# Voltage_Reference_Circuit.net
KiCad netlist of a schematic drawn in Altium Designer
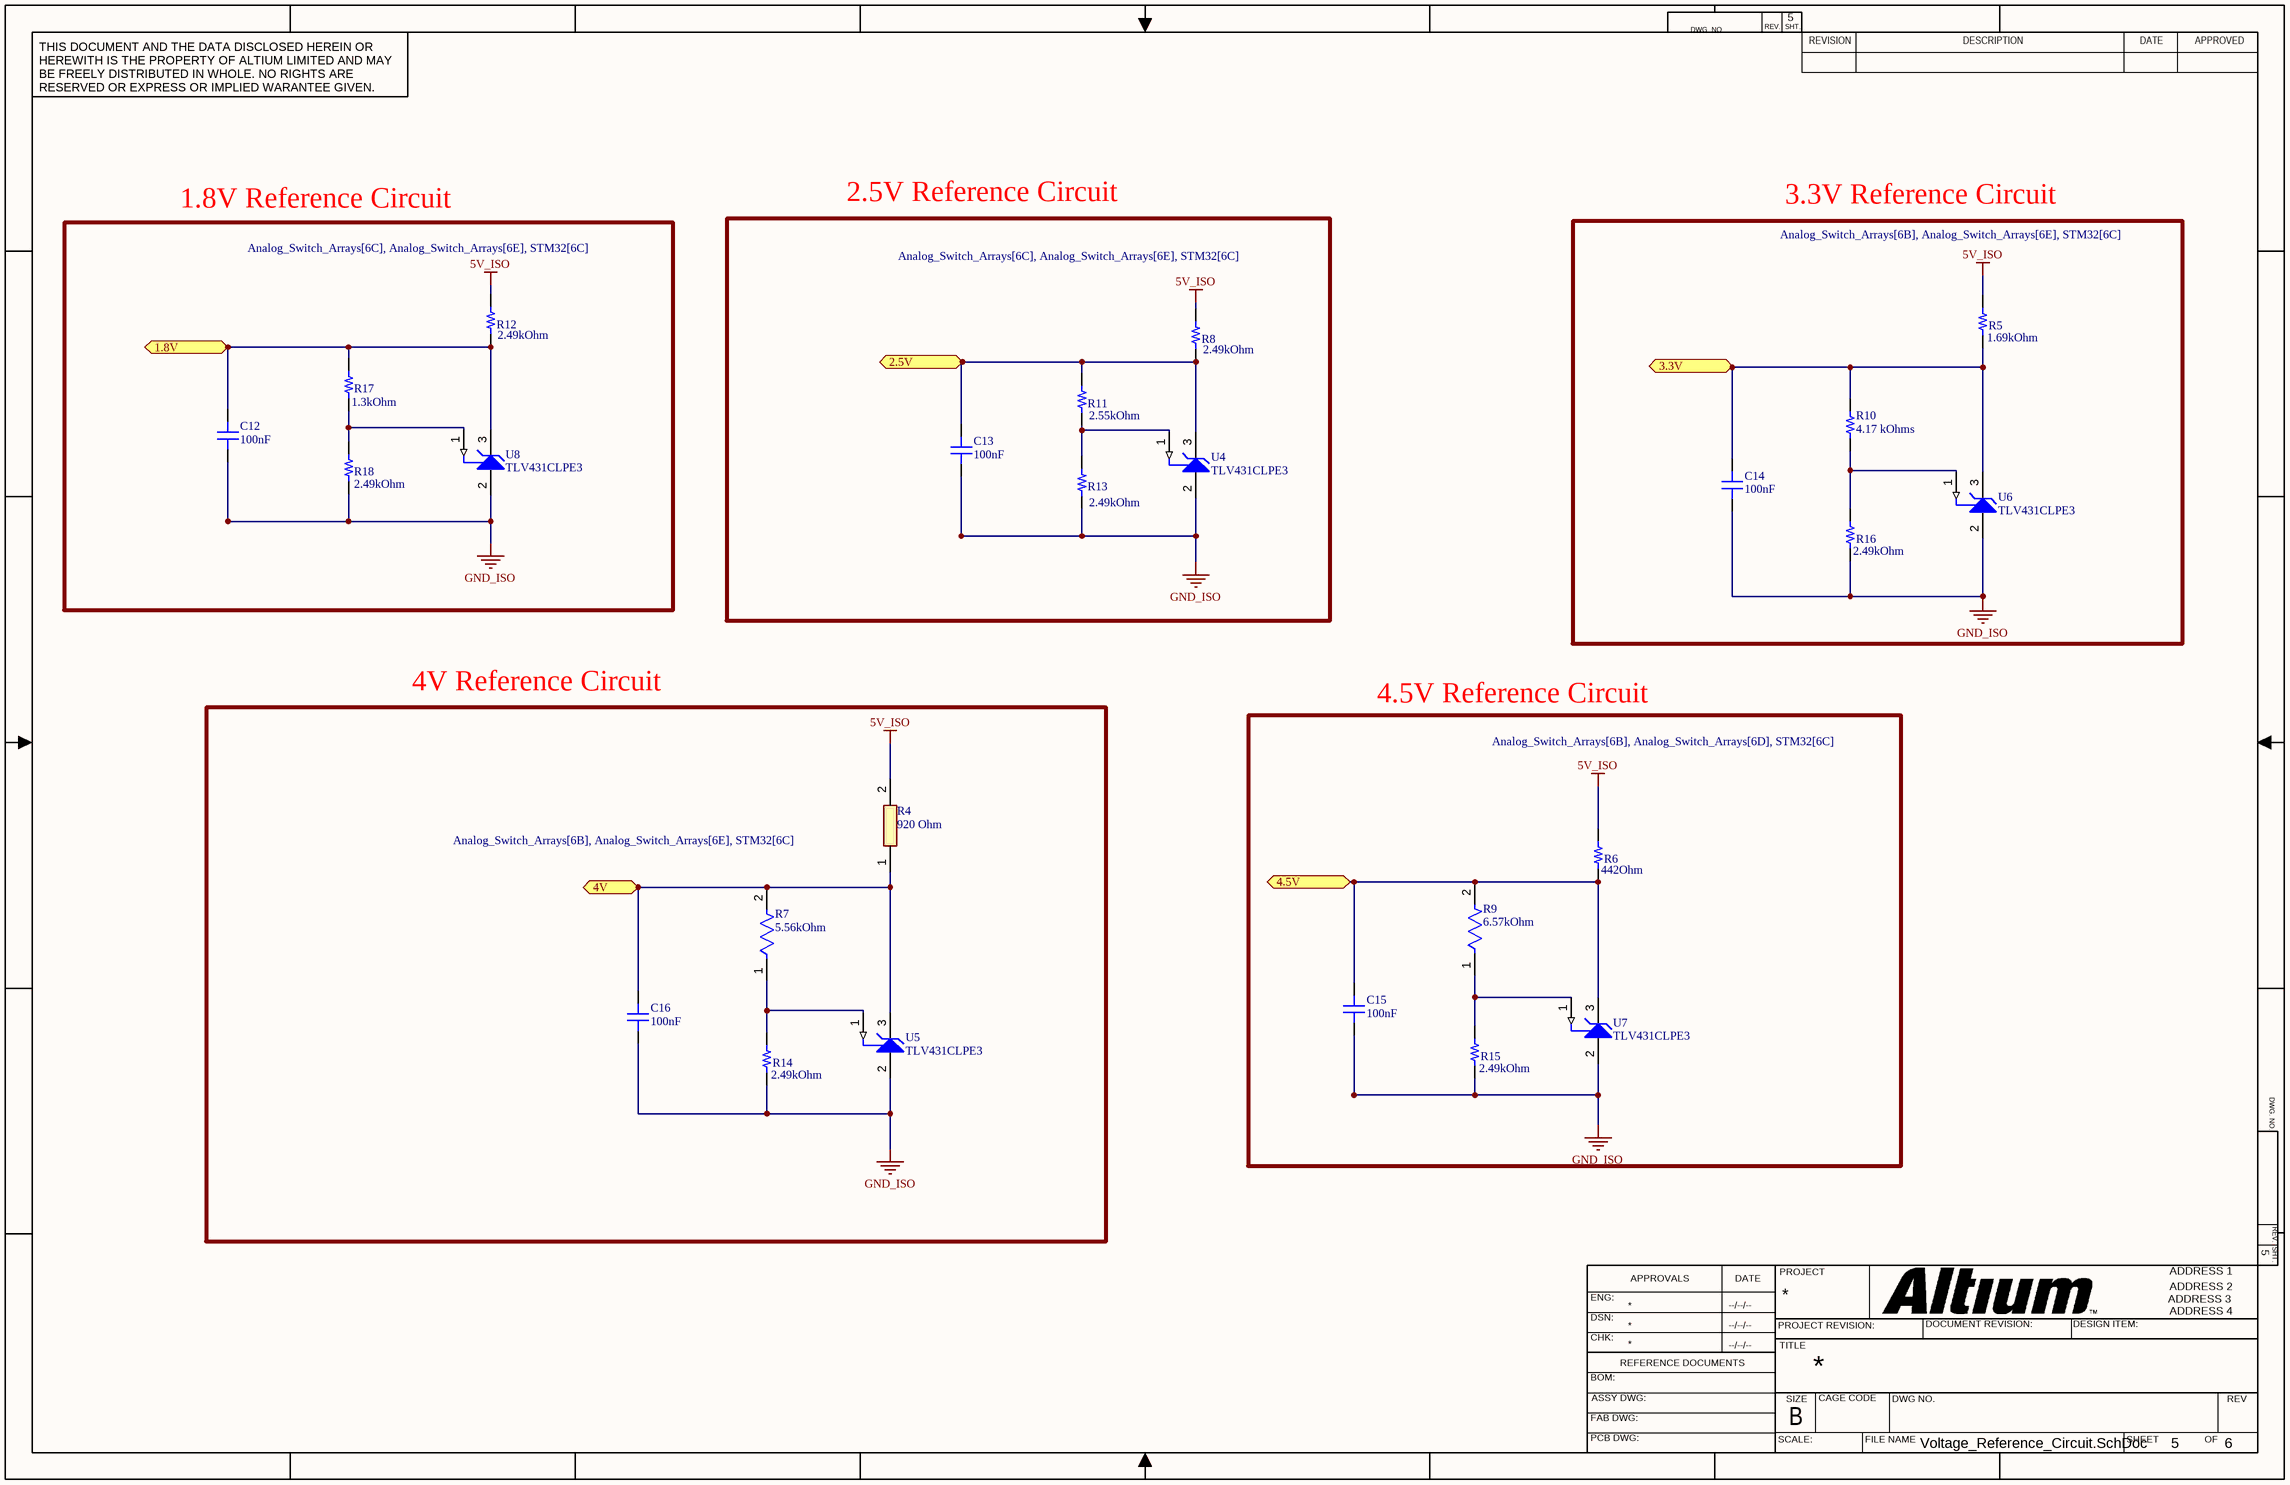
[diagram p0: Voltage_Reference_Circuit.SchDoc]

(export (version "E")
  (design (tool "Eeschema 10.0.6"))
  (components
    (comp (ref "C12")
      (value "100nF")
      (footprint "CAP 1206_3216 - 0.8MM")
      (description "CAP CER 0.1UF 25V X7R 1206")
      (fields (field (name "PART NUMBER") "VJ1206Y104KXXAC"))
      (libsource (lib "University of Massachusetts Lowell") (part "CAPACITOR"))
    )
    (comp (ref "C13")
      (value "100nF")
      (footprint "CAP 1206_3216 - 0.8MM")
      (description "CAP CER 0.1UF 25V X7R 1206")
      (fields (field (name "PART NUMBER") "VJ1206Y104KXXAC"))
      (libsource (lib "University of Massachusetts Lowell") (part "CAPACITOR"))
    )
    (comp (ref "C14")
      (value "100nF")
      (footprint "CAP 1206_3216 - 0.8MM")
      (description "CAP CER 0.1UF 25V X7R 1206")
      (fields (field (name "PART NUMBER") "VJ1206Y104KXXAC"))
      (libsource (lib "University of Massachusetts Lowell") (part "CAPACITOR"))
    )
    (comp (ref "C15")
      (value "100nF")
      (footprint "CAP 1206_3216 - 0.8MM")
      (description "CAP CER 0.1UF 25V X7R 1206")
      (fields (field (name "PART NUMBER") "VJ1206Y104KXXAC"))
      (libsource (lib "University of Massachusetts Lowell") (part "CAPACITOR"))
    )
    (comp (ref "C16")
      (value "100nF")
      (footprint "CAP 1206_3216 - 0.8MM")
      (description "CAP CER 0.1UF 25V X7R 1206")
      (fields (field (name "PART NUMBER") "VJ1206Y104KXXAC"))
      (libsource (lib "University of Massachusetts Lowell") (part "CAPACITOR"))
    )
    (comp (ref "R4")
      (value "920 Ohm")
      (footprint "SamacSys:RESC1608X55N")
      (description "Resistor")
      (fields (field (name "MANUFACTURER_PART_NUMBER") "UPTF0603-16W-N-1781FT"))
      (libsource (lib "*") (part "UPTF0603-16W-N-1781FT"))
    )
    (comp (ref "R5")
      (value "1.69kOhm")
      (footprint "RES 1206_3216")
      (description "RES 1.69 KOHMS 0.1% 0.4W 1206")
      (fields (field (name "PART NUMBER") "RQ73C2B1K69BTD"))
      (libsource (lib "University of Massachusetts Lowell") (part "RESISTOR"))
    )
    (comp (ref "R6")
      (value "442Ohm")
      (footprint "YAGEO RES 1206_3216")
      (description "RES SMD 442 OHM 0.1% 1/4W 1206")
      (fields (field (name "PART NUMBER") "RT1206BRD07442RL"))
      (libsource (lib "University of Massachusetts Lowell") (part "RESISTOR"))
    )
    (comp (ref "R7")
      (value "5.56kOhm")
      (footprint "FP-RN73R2A-IPC_C")
      (description "5.56kΩ ±0.1% 0.125W, 1/8W Chip Resistor 0805 (2012 Metric) Moisture Resistant Thin Film")
      (libsource (lib "Altium Content Vault") (part "1029c3af85768c4190bb7ad29bc67b5"))
    )
    (comp (ref "R8")
      (value "2.49kOhm")
      (footprint "RES 1206_3216")
      (description "RES SMD 2.49K OHM 1% 1/4W 1206")
      (fields (field (name "PART NUMBER") "KTR18EZPF2491"))
      (libsource (lib "University of Massachusetts Lowell") (part "RESISTOR"))
    )
    (comp (ref "R9")
      (value "6.57kOhm")
      (footprint "FP-CRCW1206-e3-IPC_B")
      (description "RES Thick Film, 6.57kΩ, 1%, 0.25W, 100ppm/°C, 1206")
      (fields (field (name "TOLERANCE") "1%"))
      (libsource (lib "Altium Content Vault") (part "1029c3af85768c4190bb7ad29bc67b5"))
    )
    (comp (ref "R10")
      (value "4.17 kOhms")
      (footprint "KOA RES RK73 RN73 0603_1608")
      (description "RES 4.17K OHM 0.1% 1/10W 0603")
      (fields (field (name "PART NUMBER") "RN73R1JTTD4171B25"))
      (libsource (lib "University of Massachusetts Lowell") (part "RESISTOR"))
    )
    (comp (ref "R11")
      (value "2.55kOhm")
      (footprint "YAGEO RES 1206_3216")
      (description "RES SMD 2.55K OHM 0.1% 1/4W 1206")
      (fields (field (name "PART NUMBER") "RT1206BRD072K55L"))
      (libsource (lib "University of Massachusetts Lowell") (part "RESISTOR"))
    )
    (comp (ref "R12")
      (value "2.49kOhm")
      (footprint "RES 1206_3216")
      (description "RES SMD 2.49K OHM 1% 1/4W 1206")
      (fields (field (name "PART NUMBER") "KTR18EZPF2491"))
      (libsource (lib "University of Massachusetts Lowell") (part "RESISTOR"))
    )
    (comp (ref "R13")
      (value "2.49kOhm")
      (footprint "RES 1206_3216")
      (description "RES SMD 2.49K OHM 1% 1/4W 1206")
      (fields (field (name "PART NUMBER") "KTR18EZPF2491"))
      (libsource (lib "University of Massachusetts Lowell") (part "RESISTOR"))
    )
    (comp (ref "R14")
      (value "2.49kOhm")
      (footprint "RES 1206_3216")
      (description "RES SMD 2.49K OHM 1% 1/4W 1206")
      (fields (field (name "PART NUMBER") "KTR18EZPF2491"))
      (libsource (lib "University of Massachusetts Lowell") (part "RESISTOR"))
    )
    (comp (ref "R15")
      (value "2.49kOhm")
      (footprint "RES 1206_3216")
      (description "RES SMD 2.49K OHM 1% 1/4W 1206")
      (fields (field (name "PART NUMBER") "KTR18EZPF2491"))
      (libsource (lib "University of Massachusetts Lowell") (part "RESISTOR"))
    )
    (comp (ref "R16")
      (value "2.49kOhm")
      (footprint "RES 1206_3216")
      (description "RES SMD 2.49K OHM 1% 1/4W 1206")
      (fields (field (name "PART NUMBER") "KTR18EZPF2491"))
      (libsource (lib "University of Massachusetts Lowell") (part "RESISTOR"))
    )
    (comp (ref "R17")
      (value "1.3kOhm")
      (footprint "RES 1206_3216")
      (description "RES 1.13K OHM 1% 1/4W 1206")
      (fields (field (name "PART NUMBER") "RK73H2BTTD1131F"))
      (libsource (lib "University of Massachusetts Lowell") (part "RESISTOR"))
    )
    (comp (ref "R18")
      (value "2.49kOhm")
      (footprint "RES 1206_3216")
      (description "RES SMD 2.49K OHM 1% 1/4W 1206")
      (fields (field (name "PART NUMBER") "KTR18EZPF2491"))
      (libsource (lib "University of Massachusetts Lowell") (part "RESISTOR"))
    )
    (comp (ref "U4")
      (value "TLV431CLPE3")
      (footprint "TI-LP3")
      (fields (field (name "MANUFACTURER") "Texas Instruments"))
      (libsource (lib "Altium Content Vault") (part "TI-TLV431LP3"))
    )
    (comp (ref "U5")
      (value "TLV431CLPE3")
      (footprint "TI-LP3")
      (fields (field (name "MANUFACTURER") "Texas Instruments"))
      (libsource (lib "Altium Content Vault") (part "TI-TLV431LP3"))
    )
    (comp (ref "U6")
      (value "TLV431CLPE3")
      (footprint "TI-LP3")
      (fields (field (name "MANUFACTURER") "Texas Instruments"))
      (libsource (lib "Altium Content Vault") (part "TI-TLV431LP3"))
    )
    (comp (ref "U7")
      (value "TLV431CLPE3")
      (footprint "TI-LP3")
      (fields (field (name "MANUFACTURER") "Texas Instruments"))
      (libsource (lib "Altium Content Vault") (part "TI-TLV431LP3"))
    )
    (comp (ref "U8")
      (value "TLV431CLPE3")
      (footprint "TI-LP3")
      (fields (field (name "MANUFACTURER") "Texas Instruments"))
      (libsource (lib "Altium Content Vault") (part "TI-TLV431LP3"))
    )
  )
  (nets
    (net (code "1") (name "/1.8V") (class "Default")
      (node (ref "C12") (pin "2") (pinfunction "2_2") (pintype "passive"))
      (node (ref "R12") (pin "1") (pinfunction "1_1") (pintype "passive"))
      (node (ref "R17") (pin "2") (pinfunction "2_2") (pintype "passive"))
      (node (ref "U8") (pin "3") (pinfunction "CATHODE_3") (pintype "passive"))
    )
    (net (code "2") (name "/2.5V") (class "Default")
      (node (ref "C13") (pin "2") (pinfunction "2_2") (pintype "passive"))
      (node (ref "R11") (pin "2") (pinfunction "2_2") (pintype "passive"))
      (node (ref "R8") (pin "1") (pinfunction "1_1") (pintype "passive"))
      (node (ref "U4") (pin "3") (pinfunction "CATHODE_3") (pintype "passive"))
    )
    (net (code "3") (name "/3.3V") (class "Default")
      (node (ref "C14") (pin "2") (pinfunction "2_2") (pintype "passive"))
      (node (ref "R10") (pin "2") (pinfunction "2_2") (pintype "passive"))
      (node (ref "R5") (pin "1") (pinfunction "1_1") (pintype "passive"))
      (node (ref "U6") (pin "3") (pinfunction "CATHODE_3") (pintype "passive"))
    )
    (net (code "4") (name "/4.5V") (class "Default")
      (node (ref "C15") (pin "2") (pinfunction "2_2") (pintype "passive"))
      (node (ref "R6") (pin "1") (pinfunction "1_1") (pintype "passive"))
      (node (ref "R9") (pin "2") (pinfunction "2_2") (pintype "passive"))
      (node (ref "U7") (pin "3") (pinfunction "CATHODE_3") (pintype "passive"))
    )
    (net (code "5") (name "/4V") (class "Default")
      (node (ref "C16") (pin "2") (pinfunction "2_2") (pintype "passive"))
      (node (ref "R4") (pin "1") (pinfunction "1_1") (pintype "passive"))
      (node (ref "R7") (pin "2") (pinfunction "2_2") (pintype "passive"))
      (node (ref "U5") (pin "3") (pinfunction "CATHODE_3") (pintype "passive"))
    )
    (net (code "6") (name "5V_ISO") (class "Default")
      (node (ref "R12") (pin "2") (pinfunction "2_2") (pintype "passive"))
      (node (ref "R4") (pin "2") (pinfunction "2_2") (pintype "passive"))
      (node (ref "R5") (pin "2") (pinfunction "2_2") (pintype "passive"))
      (node (ref "R6") (pin "2") (pinfunction "2_2") (pintype "passive"))
      (node (ref "R8") (pin "2") (pinfunction "2_2") (pintype "passive"))
    )
    (net (code "7") (name "GND_ISO") (class "Default")
      (node (ref "C12") (pin "1") (pinfunction "1_1") (pintype "passive"))
      (node (ref "C13") (pin "1") (pinfunction "1_1") (pintype "passive"))
      (node (ref "C14") (pin "1") (pinfunction "1_1") (pintype "passive"))
      (node (ref "C15") (pin "1") (pinfunction "1_1") (pintype "passive"))
      (node (ref "C16") (pin "1") (pinfunction "1_1") (pintype "passive"))
      (node (ref "R13") (pin "1") (pinfunction "1_1") (pintype "passive"))
      (node (ref "R14") (pin "1") (pinfunction "1_1") (pintype "passive"))
      (node (ref "R15") (pin "1") (pinfunction "1_1") (pintype "passive"))
      (node (ref "R16") (pin "1") (pinfunction "1_1") (pintype "passive"))
      (node (ref "R18") (pin "1") (pinfunction "1_1") (pintype "passive"))
      (node (ref "U4") (pin "2") (pinfunction "ANODE_2") (pintype "passive"))
      (node (ref "U5") (pin "2") (pinfunction "ANODE_2") (pintype "passive"))
      (node (ref "U6") (pin "2") (pinfunction "ANODE_2") (pintype "passive"))
      (node (ref "U7") (pin "2") (pinfunction "ANODE_2") (pintype "passive"))
      (node (ref "U8") (pin "2") (pinfunction "ANODE_2") (pintype "passive"))
    )
    (net (code "8") (name "Net-(U4-REF)") (class "Default")
      (node (ref "R11") (pin "1") (pinfunction "1_1") (pintype "passive"))
      (node (ref "R13") (pin "2") (pinfunction "2_2") (pintype "passive"))
      (node (ref "U4") (pin "1") (pinfunction "REF_1") (pintype "input"))
    )
    (net (code "9") (name "Net-(U5-REF)") (class "Default")
      (node (ref "R14") (pin "2") (pinfunction "2_2") (pintype "passive"))
      (node (ref "R7") (pin "1") (pinfunction "1_1") (pintype "passive"))
      (node (ref "U5") (pin "1") (pinfunction "REF_1") (pintype "input"))
    )
    (net (code "10") (name "Net-(U6-REF)") (class "Default")
      (node (ref "R10") (pin "1") (pinfunction "1_1") (pintype "passive"))
      (node (ref "R16") (pin "2") (pinfunction "2_2") (pintype "passive"))
      (node (ref "U6") (pin "1") (pinfunction "REF_1") (pintype "input"))
    )
    (net (code "11") (name "Net-(U7-REF)") (class "Default")
      (node (ref "R15") (pin "2") (pinfunction "2_2") (pintype "passive"))
      (node (ref "R9") (pin "1") (pinfunction "1_1") (pintype "passive"))
      (node (ref "U7") (pin "1") (pinfunction "REF_1") (pintype "input"))
    )
    (net (code "12") (name "Net-(U8-REF)") (class "Default")
      (node (ref "R17") (pin "1") (pinfunction "1_1") (pintype "passive"))
      (node (ref "R18") (pin "2") (pinfunction "2_2") (pintype "passive"))
      (node (ref "U8") (pin "1") (pinfunction "REF_1") (pintype "input"))
    )
  )
)
